# GrandMini_v1.net
KiCad netlist of a schematic drawn in Altium Designer
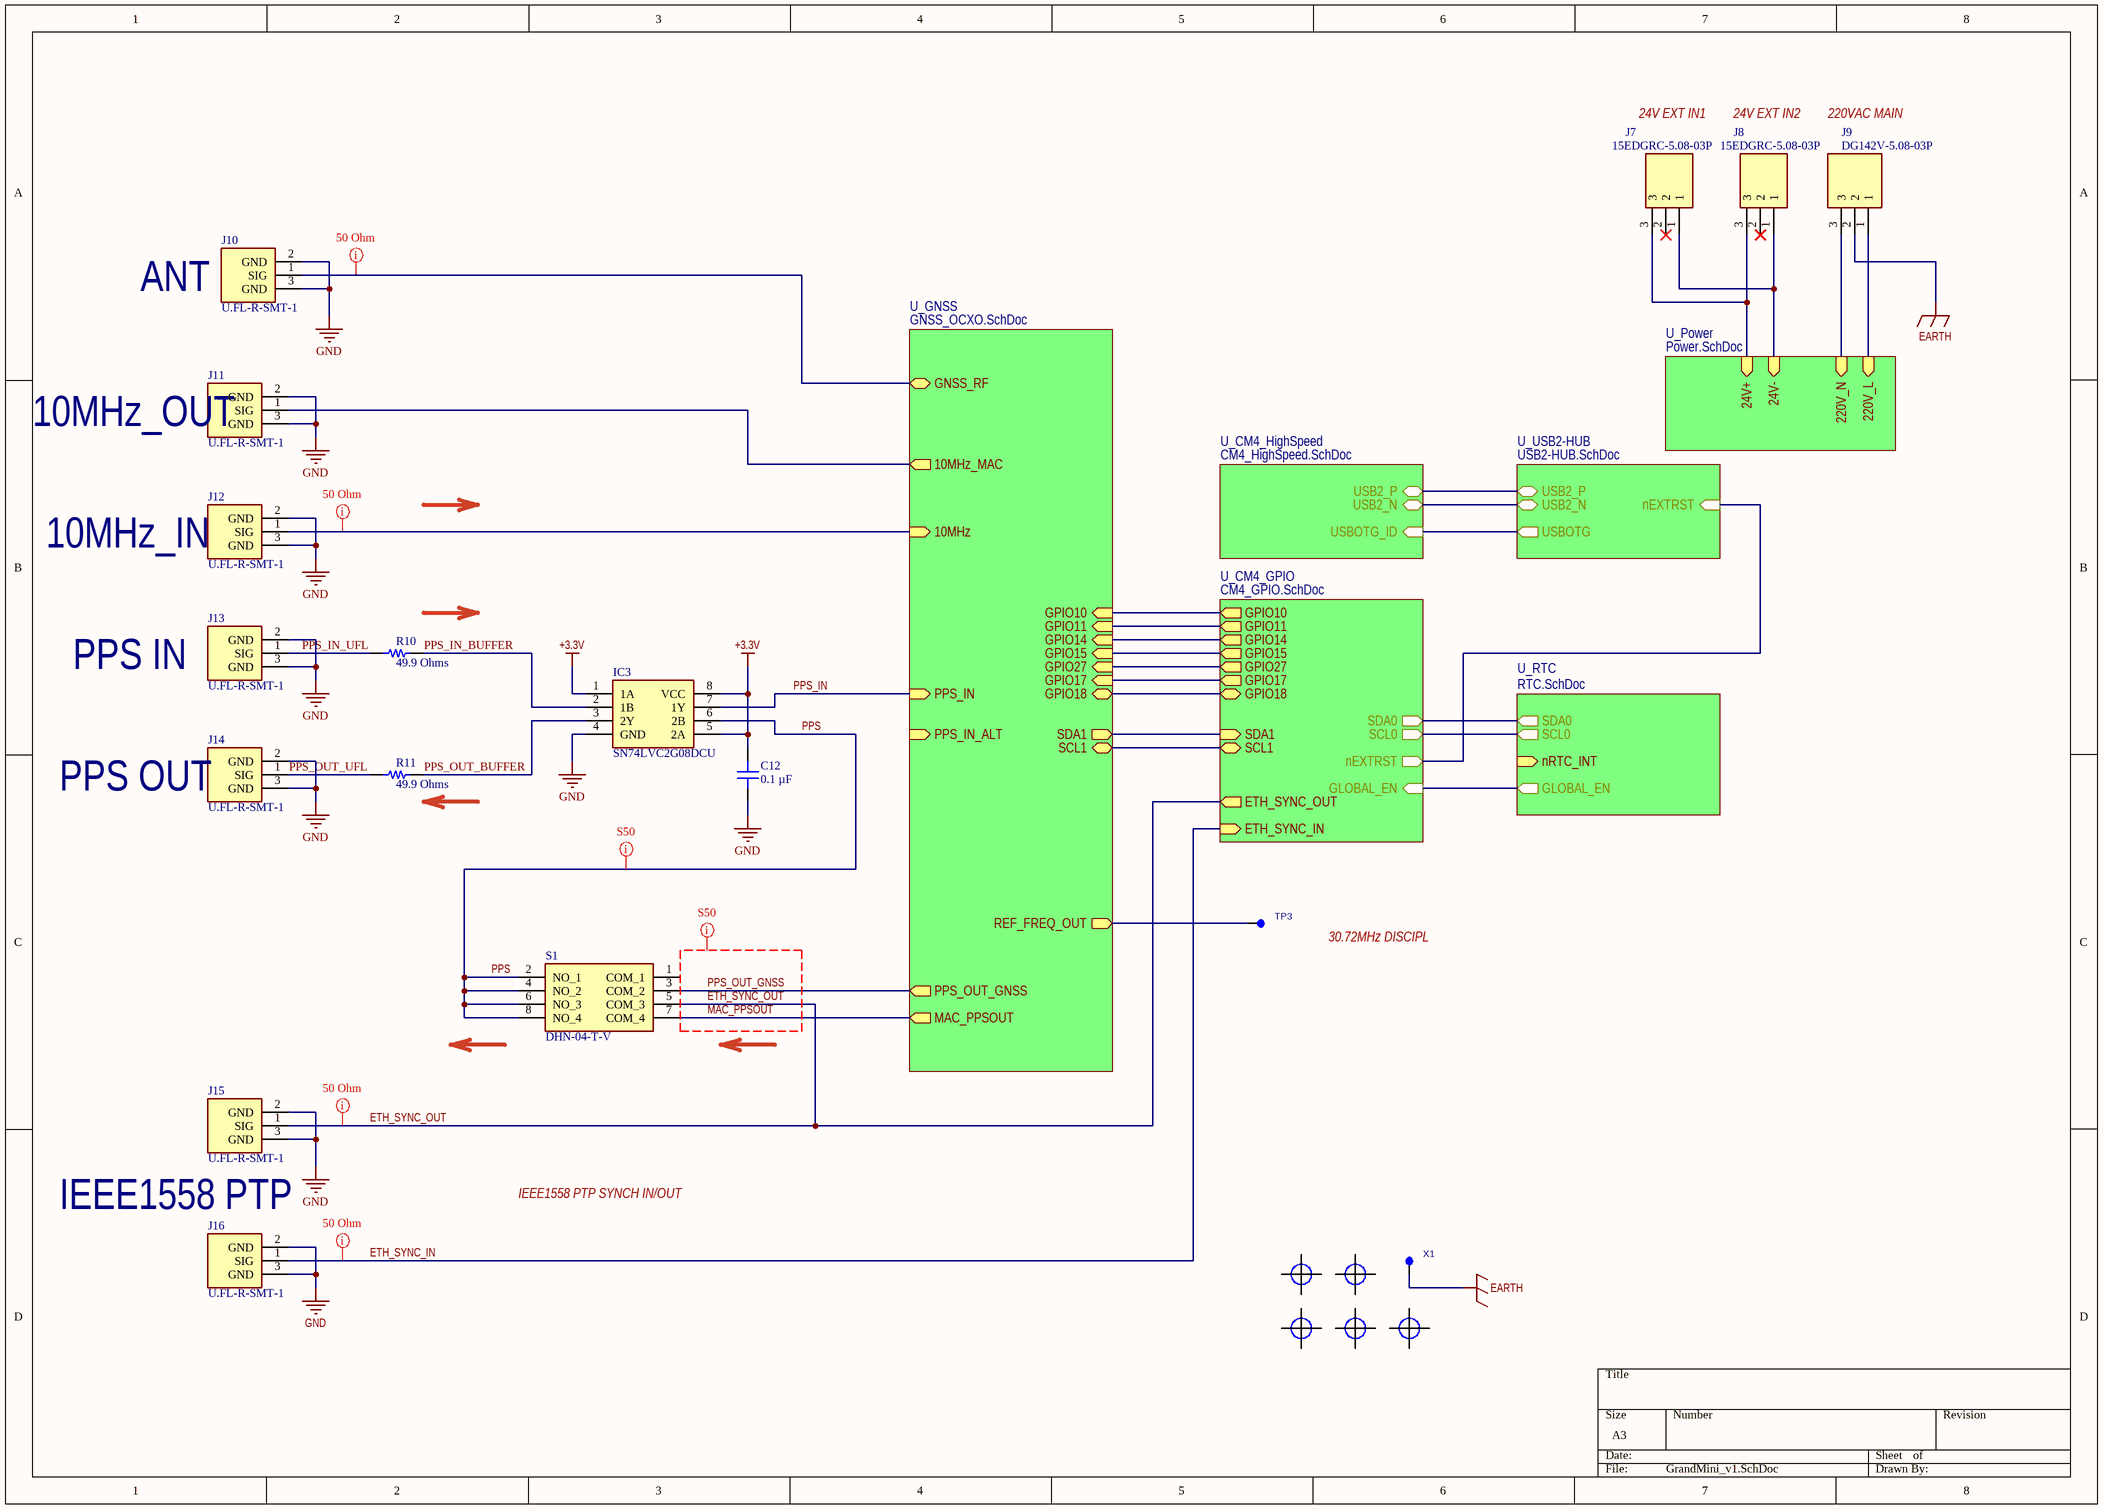
[diagram p0: GrandMini_v1.SchDoc]

(export (version "E")
  (design (tool "Eeschema 10.0.6"))
  (components
    (comp (ref "C12")
      (value "0.1 µF")
      (footprint "CAP 0603_1608")
      (description "CAP CER 0.1UF 50V X7R 0603")
      (fields (field (name "MANUFACTURER") "Yageo") (field (name "TOLERANCE") "±10%"))
      (libsource (lib "Celestial Altium Library - altium_library") (part "Capacitor"))
    )
    (comp (ref "IC3")
      (value "SN74LVC2G08DCU")
      (footprint "SamacSys:SOP50P310X90-8N")
      (description "Integrated Circuit")
      (libsource (lib "SamacSys") (part "SN74LVC2G08DCU"))
    )
    (comp (ref "J7")
      (value "15EDGRC-5.08-03P")
      (footprint "SamacSys:15EDGRC-5.08-03P")
      (description "Connector")
      (fields (field (name "MANUFACTURER_PART_NUMBER") "15EDGRC-5.08-02P-14-00A(H)"))
      (libsource (lib "SamacSys") (part "15EDGRC-5.08-03P"))
    )
    (comp (ref "J8")
      (value "15EDGRC-5.08-03P")
      (footprint "SamacSys:15EDGRC-5.08-03P")
      (description "Connector")
      (fields (field (name "MANUFACTURER_PART_NUMBER") "15EDGRC-5.08-02P-14-00A(H)"))
      (libsource (lib "SamacSys") (part "15EDGRC-5.08-03P"))
    )
    (comp (ref "J9")
      (value "DG142V-5.08-03P")
      (footprint "SamacSys:DG142V-5.08-03P")
      (description "Connector")
      (fields (field (name "MANUFACTURER_PART_NUMBER") "DG142V-5.08-02P"))
      (libsource (lib "SamacSys") (part "DG142V-5.08-03P_1"))
    )
    (comp (ref "J10")
      (value "U.FL-R-SMT-1")
      (footprint "SamacSys:U.FL-R-SMT-1")
      (description "Connector")
      (libsource (lib "SamacSys") (part "U.FL-R-SMT-1"))
    )
    (comp (ref "J11")
      (value "U.FL-R-SMT-1")
      (footprint "SamacSys:U.FL-R-SMT-1")
      (description "Connector")
      (libsource (lib "SamacSys") (part "U.FL-R-SMT-1"))
    )
    (comp (ref "J12")
      (value "U.FL-R-SMT-1")
      (footprint "SamacSys:U.FL-R-SMT-1")
      (description "Connector")
      (libsource (lib "SamacSys") (part "U.FL-R-SMT-1"))
    )
    (comp (ref "J13")
      (value "U.FL-R-SMT-1")
      (footprint "SamacSys:U.FL-R-SMT-1")
      (description "Connector")
      (libsource (lib "SamacSys") (part "U.FL-R-SMT-1"))
    )
    (comp (ref "J14")
      (value "U.FL-R-SMT-1")
      (footprint "SamacSys:U.FL-R-SMT-1")
      (description "Connector")
      (libsource (lib "SamacSys") (part "U.FL-R-SMT-1"))
    )
    (comp (ref "J15")
      (value "U.FL-R-SMT-1")
      (footprint "SamacSys:U.FL-R-SMT-1")
      (description "Connector")
      (libsource (lib "SamacSys") (part "U.FL-R-SMT-1"))
    )
    (comp (ref "J16")
      (value "U.FL-R-SMT-1")
      (footprint "SamacSys:U.FL-R-SMT-1")
      (description "Connector")
      (libsource (lib "SamacSys") (part "U.FL-R-SMT-1"))
    )
    (comp (ref "MNT1")
      (value "MOUNT_HOLE")
      (footprint "SamacSys:MOUNT_3.5mm")
      (description "Mount hole")
      (libsource (lib "SamacSys") (part "MOUNT_HOLE"))
    )
    (comp (ref "MNT2")
      (value "MOUNT_HOLE")
      (footprint "SamacSys:MOUNT_3.5mm")
      (description "Mount hole")
      (libsource (lib "SamacSys") (part "MOUNT_HOLE"))
    )
    (comp (ref "MNT4")
      (value "MOUNT_HOLE")
      (footprint "SamacSys:MOUNT_3.5mm")
      (description "Mount hole")
      (libsource (lib "SamacSys") (part "MOUNT_HOLE"))
    )
    (comp (ref "MNT5")
      (value "MOUNT_HOLE")
      (footprint "SamacSys:MOUNT_3.5mm")
      (description "Mount hole")
      (libsource (lib "SamacSys") (part "MOUNT_HOLE"))
    )
    (comp (ref "MNT6")
      (value "MOUNT_HOLE")
      (footprint "SamacSys:MOUNT_3.5mm")
      (description "Mount hole")
      (libsource (lib "SamacSys") (part "MOUNT_HOLE"))
    )
    (comp (ref "R10")
      (value "49.9 Ohms")
      (footprint "YAGEO RES 0603_1608")
      (description "RES 49.9 OHM 1% 1/10W 0603")
      (fields (field (name "PART NUMBER") "RC0603FR-0749R9L") (field (name "MANUFACTURER") "Yageo"))
      (libsource (lib "Celestial Altium Library - altium_library") (part "Resistor"))
    )
    (comp (ref "R11")
      (value "49.9 Ohms")
      (footprint "YAGEO RES 0603_1608")
      (description "RES 49.9 OHM 1% 1/10W 0603")
      (fields (field (name "PART NUMBER") "RC0603FR-0749R9L") (field (name "MANUFACTURER") "Yageo"))
      (libsource (lib "Celestial Altium Library - altium_library") (part "Resistor"))
    )
    (comp (ref "S1")
      (value "DHN-04-T-V")
      (footprint "SamacSys:DHN04TV")
      (description "Switch")
      (fields (field (name "MOUSER PART NUMBER") "113-DHN04TV"))
      (libsource (lib "SamacSys") (part "DHN-04-T-V"))
    )
    (comp (ref "TP3")
      (value "30.72MHz")
      (footprint "Samacsys:PAD_TEST")
      (description "Test Point")
      (fields (field (name "TOLERANCE") "{Tolerance}") (field (name "MANUFACTURER") "{Manufacturer}"))
      (libsource (lib "SamacSys") (part "PAD_TEST"))
    )
    (comp (ref "X1")
      (value "PAD")
      (footprint "samacsys:POWERPAD_ROU_7/3.2")
      (description "Power Pad")
      (fields (field (name "TOLERANCE") "{Tolerance}") (field (name "MANUFACTURER") "{Manufacturer}"))
      (libsource (lib "SamacSys") (part "PAD"))
    )
  )
  (nets
    (net (code "1") (name "+3.3V") (class "Default")
      (node (ref "C12") (pin "2") (pinfunction "2_2") (pintype "passive"))
      (node (ref "IC3") (pin "1") (pinfunction "1A_1") (pintype "passive"))
      (node (ref "IC3") (pin "5") (pinfunction "2A_5") (pintype "passive"))
      (node (ref "IC3") (pin "8") (pinfunction "VCC_8") (pintype "passive"))
    )
    (net (code "2") (name "/10MHz") (class "Default")
      (node (ref "J12") (pin "1") (pinfunction "SIG_1") (pintype "passive"))
    )
    (net (code "3") (name "/10MHz_MAC") (class "Default")
      (node (ref "J11") (pin "1") (pinfunction "SIG_1") (pintype "passive"))
    )
    (net (code "4") (name "/24V+") (class "Default")
      (node (ref "J7") (pin "3") (pinfunction "3_3") (pintype "passive"))
      (node (ref "J8") (pin "3") (pinfunction "3_3") (pintype "passive"))
    )
    (net (code "5") (name "/24V-") (class "Default")
      (node (ref "J7") (pin "1") (pinfunction "1_1") (pintype "passive"))
      (node (ref "J8") (pin "1") (pinfunction "1_1") (pintype "passive"))
    )
    (net (code "6") (name "/220V_L") (class "Default")
      (node (ref "J9") (pin "1") (pinfunction "1_1") (pintype "passive"))
    )
    (net (code "7") (name "/220V_N") (class "Default")
      (node (ref "J9") (pin "3") (pinfunction "3_3") (pintype "passive"))
    )
    (net (code "8") (name "/ETH_SYNC_IN") (class "Default")
      (node (ref "J16") (pin "1") (pinfunction "SIG_1") (pintype "passive"))
    )
    (net (code "9") (name "/ETH_SYNC_OUT") (class "Default")
      (node (ref "J15") (pin "1") (pinfunction "SIG_1") (pintype "passive"))
      (node (ref "S1") (pin "5") (pinfunction "COM_3_5") (pintype "passive"))
    )
    (net (code "11") (name "/GNSS_RF") (class "Default")
      (node (ref "J10") (pin "1") (pinfunction "SIG_1") (pintype "passive"))
    )
    (net (code "19") (name "/MAC_PPSOUT") (class "Default")
      (node (ref "S1") (pin "7") (pinfunction "COM_4_7") (pintype "passive"))
    )
    (net (code "20") (name "/PPS") (class "Default")
      (node (ref "IC3") (pin "6") (pinfunction "2B_6") (pintype "passive"))
      (node (ref "S1") (pin "2") (pinfunction "NO_1_2") (pintype "passive"))
      (node (ref "S1") (pin "4") (pinfunction "NO_2_4") (pintype "passive"))
      (node (ref "S1") (pin "6") (pinfunction "NO_3_6") (pintype "passive"))
      (node (ref "S1") (pin "8") (pinfunction "NO_4_8") (pintype "passive"))
    )
    (net (code "21") (name "/PPS_IN") (class "Default")
      (node (ref "IC3") (pin "7") (pinfunction "1Y_7") (pintype "passive"))
    )
    (net (code "23") (name "/PPS_IN_BUFFER") (class "Default")
      (node (ref "IC3") (pin "2") (pinfunction "1B_2") (pintype "passive"))
      (node (ref "R10") (pin "2") (pinfunction "2_2") (pintype "passive"))
    )
    (net (code "24") (name "/PPS_IN_UFL") (class "Default")
      (node (ref "J13") (pin "1") (pinfunction "SIG_1") (pintype "passive"))
      (node (ref "R10") (pin "1") (pinfunction "1_1") (pintype "passive"))
    )
    (net (code "25") (name "/PPS_OUT_BUFFER") (class "Default")
      (node (ref "IC3") (pin "3") (pinfunction "2Y_3") (pintype "passive"))
      (node (ref "R11") (pin "2") (pinfunction "2_2") (pintype "passive"))
    )
    (net (code "26") (name "/PPS_OUT_GNSS") (class "Default")
      (node (ref "S1") (pin "3") (pinfunction "COM_2_3") (pintype "passive"))
    )
    (net (code "27") (name "/PPS_OUT_UFL") (class "Default")
      (node (ref "J14") (pin "1") (pinfunction "SIG_1") (pintype "passive"))
      (node (ref "R11") (pin "1") (pinfunction "1_1") (pintype "passive"))
    )
    (net (code "28") (name "/REF_FREQ_OUT") (class "Default")
      (node (ref "TP3") (pin "1") (pinfunction "1_1") (pintype "passive"))
    )
    (net (code "38") (name "EARTH") (class "Default")
      (node (ref "J9") (pin "2") (pinfunction "2_2") (pintype "passive"))
      (node (ref "X1") (pin "1") (pinfunction "1_1") (pintype "passive"))
    )
    (net (code "39") (name "GND") (class "Default")
      (node (ref "C12") (pin "1") (pinfunction "1_1") (pintype "passive"))
      (node (ref "IC3") (pin "4") (pinfunction "GND_4") (pintype "passive"))
      (node (ref "J10") (pin "2") (pinfunction "GND_2") (pintype "passive"))
      (node (ref "J10") (pin "3") (pinfunction "GND_3") (pintype "passive"))
      (node (ref "J11") (pin "2") (pinfunction "GND_2") (pintype "passive"))
      (node (ref "J11") (pin "3") (pinfunction "GND_3") (pintype "passive"))
      (node (ref "J12") (pin "2") (pinfunction "GND_2") (pintype "passive"))
      (node (ref "J12") (pin "3") (pinfunction "GND_3") (pintype "passive"))
      (node (ref "J13") (pin "2") (pinfunction "GND_2") (pintype "passive"))
      (node (ref "J13") (pin "3") (pinfunction "GND_3") (pintype "passive"))
      (node (ref "J14") (pin "2") (pinfunction "GND_2") (pintype "passive"))
      (node (ref "J14") (pin "3") (pinfunction "GND_3") (pintype "passive"))
      (node (ref "J15") (pin "2") (pinfunction "GND_2") (pintype "passive"))
      (node (ref "J15") (pin "3") (pinfunction "GND_3") (pintype "passive"))
      (node (ref "J16") (pin "2") (pinfunction "GND_2") (pintype "passive"))
      (node (ref "J16") (pin "3") (pinfunction "GND_3") (pintype "passive"))
    )
    (net (code "40") (name "unconnected-(J7-Pad2)") (class "Default")
      (node (ref "J7") (pin "2") (pinfunction "2_2") (pintype "passive+no_connect"))
    )
    (net (code "41") (name "unconnected-(J8-Pad2)") (class "Default")
      (node (ref "J8") (pin "2") (pinfunction "2_2") (pintype "passive+no_connect"))
    )
    (net (code "42") (name "unconnected-(S1-COM_1-Pad1)") (class "Default")
      (node (ref "S1") (pin "1") (pinfunction "COM_1_1") (pintype "passive"))
    )
  )
)
